# HONDA_BCAN.net
KiCad netlist of a schematic drawn in EAGLE
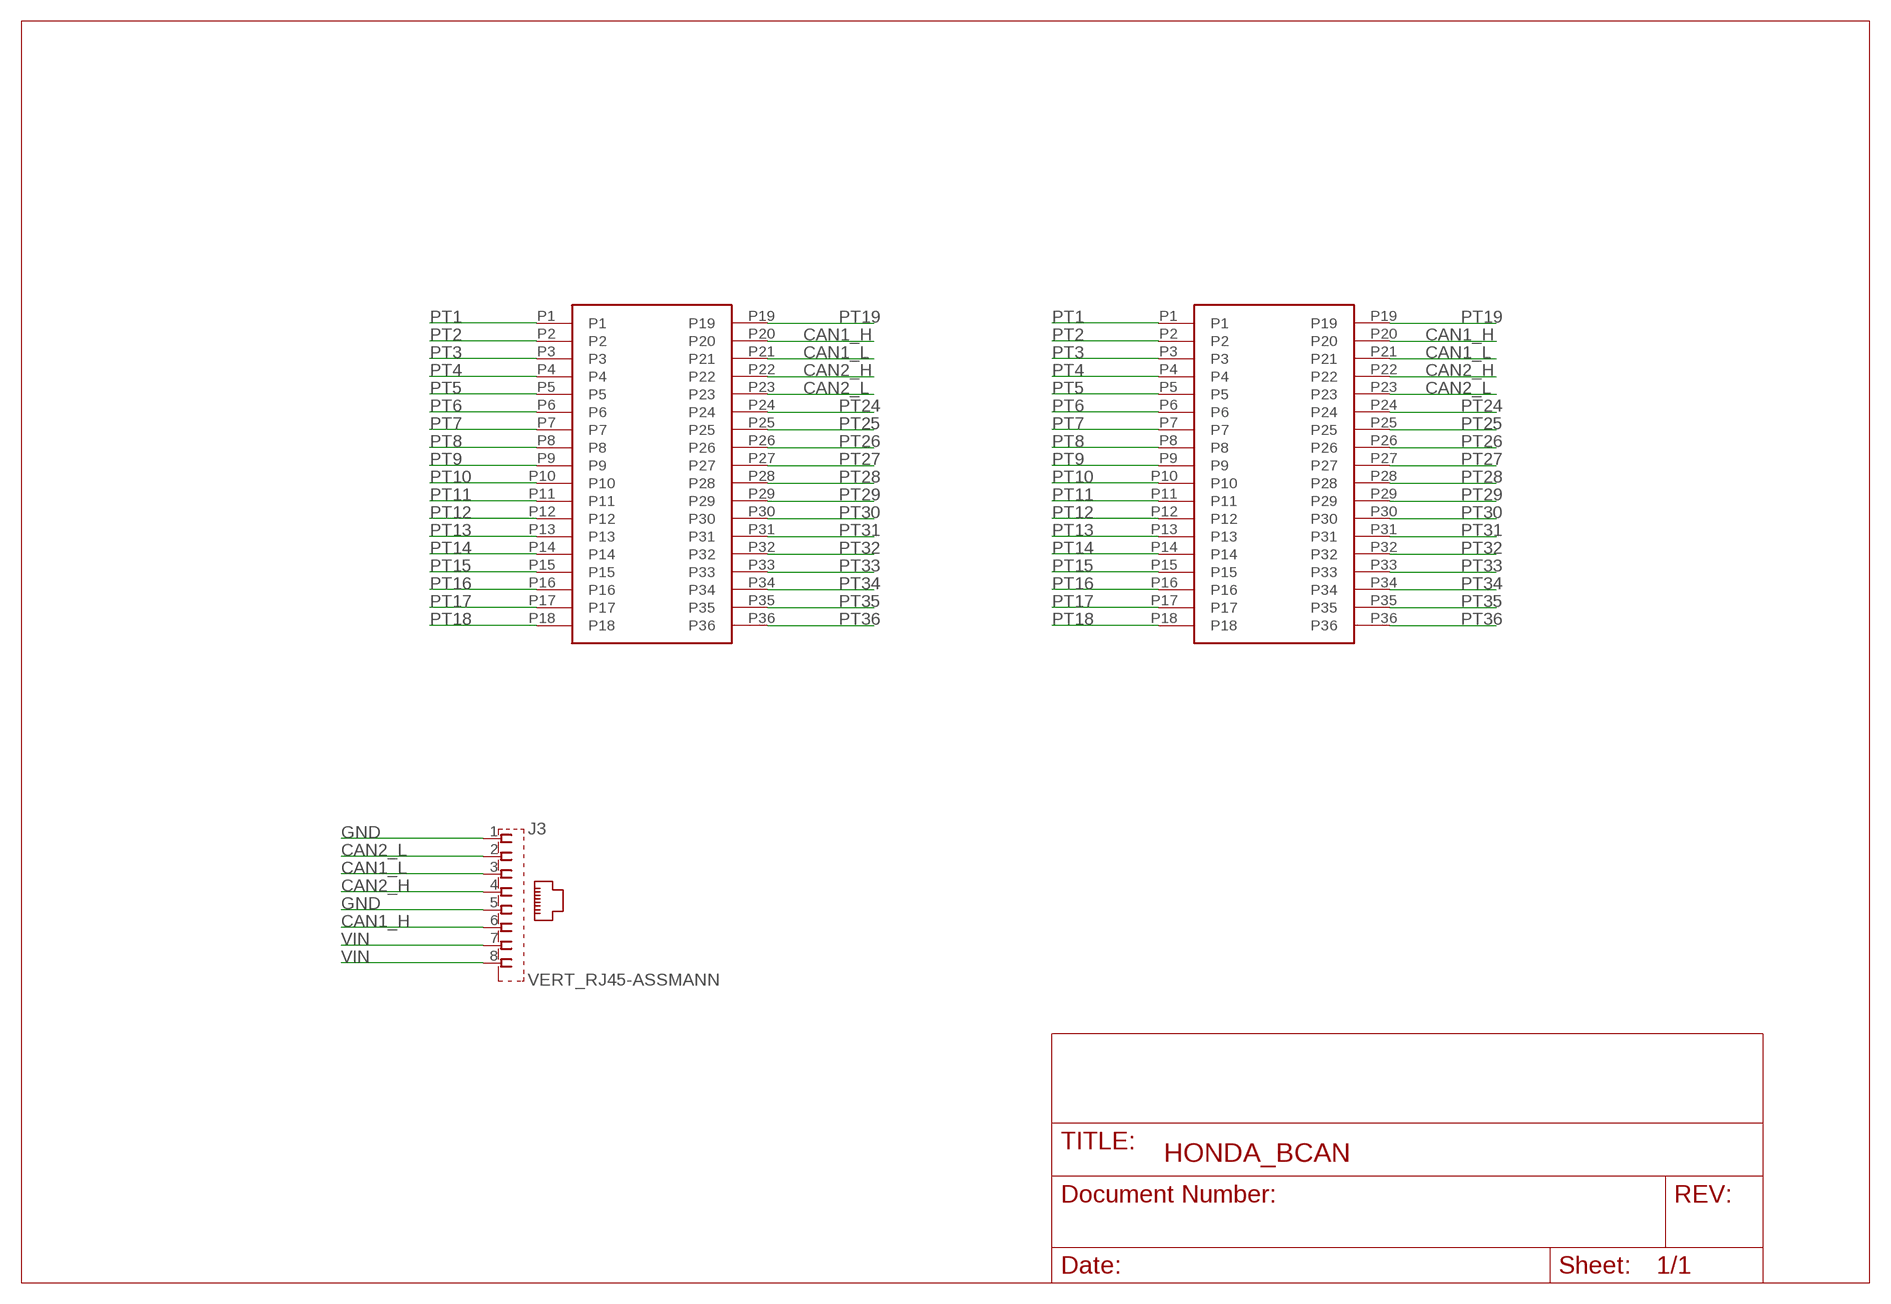
[diagram p0: schematic, sheet 1]

(export (version "E")
  (design (tool "Eeschema 10.0.6"))
  (components
    (comp (ref "J1")
      (value "MX34036NF4")
      (footprint "eagle-import:MX34036NF4")
      (libsource (lib "eagle-import") (part "MX34036NF4"))
    )
    (comp (ref "J2")
      (value "MX34036NF4")
      (footprint "eagle-import:MX34036NF4")
      (libsource (lib "eagle-import") (part "MX34036NF4"))
    )
    (comp (ref "J3")
      (value "VERT_RJ45-ASSMANN")
      (footprint "eagle-import:RJ45-VERT")
      (fields (field (name "MPN") "A-2004-2-4-LPS-N-R"))
      (libsource (lib "eagle-import") (part "VERT_RJ45-ASSMANN"))
    )
  )
  (nets
    (net (code "1") (name "/CAN1_H") (class "Default")
      (node (ref "J1") (pin "P20") (pinfunction "P20_P20") (pintype "bidirectional"))
      (node (ref "J2") (pin "P20") (pinfunction "P20_P20") (pintype "bidirectional"))
      (node (ref "J3") (pin "6") (pinfunction "6_6") (pintype "passive"))
    )
    (net (code "2") (name "/CAN1_L") (class "Default")
      (node (ref "J1") (pin "P21") (pinfunction "P21_P21") (pintype "bidirectional"))
      (node (ref "J2") (pin "P21") (pinfunction "P21_P21") (pintype "bidirectional"))
      (node (ref "J3") (pin "3") (pinfunction "3_3") (pintype "passive"))
    )
    (net (code "3") (name "/CAN2_H") (class "Default")
      (node (ref "J1") (pin "P22") (pinfunction "P22_P22") (pintype "bidirectional"))
      (node (ref "J2") (pin "P22") (pinfunction "P22_P22") (pintype "bidirectional"))
      (node (ref "J3") (pin "4") (pinfunction "4_4") (pintype "passive"))
    )
    (net (code "4") (name "/CAN2_L") (class "Default")
      (node (ref "J1") (pin "P23") (pinfunction "P23_P23") (pintype "bidirectional"))
      (node (ref "J2") (pin "P23") (pinfunction "P23_P23") (pintype "bidirectional"))
      (node (ref "J3") (pin "2") (pinfunction "2_2") (pintype "passive"))
    )
    (net (code "5") (name "/GND") (class "Default")
      (node (ref "J3") (pin "1") (pinfunction "1_1") (pintype "passive"))
      (node (ref "J3") (pin "5") (pinfunction "5_5") (pintype "passive"))
    )
    (net (code "6") (name "/PT1") (class "Default")
      (node (ref "J1") (pin "P1") (pinfunction "P1_P1") (pintype "bidirectional"))
      (node (ref "J2") (pin "P1") (pinfunction "P1_P1") (pintype "bidirectional"))
    )
    (net (code "7") (name "/PT2") (class "Default")
      (node (ref "J1") (pin "P2") (pinfunction "P2_P2") (pintype "bidirectional"))
      (node (ref "J2") (pin "P2") (pinfunction "P2_P2") (pintype "bidirectional"))
    )
    (net (code "8") (name "/PT3") (class "Default")
      (node (ref "J1") (pin "P3") (pinfunction "P3_P3") (pintype "bidirectional"))
      (node (ref "J2") (pin "P3") (pinfunction "P3_P3") (pintype "bidirectional"))
    )
    (net (code "9") (name "/PT4") (class "Default")
      (node (ref "J1") (pin "P4") (pinfunction "P4_P4") (pintype "bidirectional"))
      (node (ref "J2") (pin "P4") (pinfunction "P4_P4") (pintype "bidirectional"))
    )
    (net (code "10") (name "/PT5") (class "Default")
      (node (ref "J1") (pin "P5") (pinfunction "P5_P5") (pintype "bidirectional"))
      (node (ref "J2") (pin "P5") (pinfunction "P5_P5") (pintype "bidirectional"))
    )
    (net (code "11") (name "/PT6") (class "Default")
      (node (ref "J1") (pin "P6") (pinfunction "P6_P6") (pintype "bidirectional"))
      (node (ref "J2") (pin "P6") (pinfunction "P6_P6") (pintype "bidirectional"))
    )
    (net (code "12") (name "/PT7") (class "Default")
      (node (ref "J1") (pin "P7") (pinfunction "P7_P7") (pintype "bidirectional"))
      (node (ref "J2") (pin "P7") (pinfunction "P7_P7") (pintype "bidirectional"))
    )
    (net (code "13") (name "/PT8") (class "Default")
      (node (ref "J1") (pin "P8") (pinfunction "P8_P8") (pintype "bidirectional"))
      (node (ref "J2") (pin "P8") (pinfunction "P8_P8") (pintype "bidirectional"))
    )
    (net (code "14") (name "/PT9") (class "Default")
      (node (ref "J1") (pin "P9") (pinfunction "P9_P9") (pintype "bidirectional"))
      (node (ref "J2") (pin "P9") (pinfunction "P9_P9") (pintype "bidirectional"))
    )
    (net (code "15") (name "/PT10") (class "Default")
      (node (ref "J1") (pin "P10") (pinfunction "P10_P10") (pintype "bidirectional"))
      (node (ref "J2") (pin "P10") (pinfunction "P10_P10") (pintype "bidirectional"))
    )
    (net (code "16") (name "/PT11") (class "Default")
      (node (ref "J1") (pin "P11") (pinfunction "P11_P11") (pintype "bidirectional"))
      (node (ref "J2") (pin "P11") (pinfunction "P11_P11") (pintype "bidirectional"))
    )
    (net (code "17") (name "/PT12") (class "Default")
      (node (ref "J1") (pin "P12") (pinfunction "P12_P12") (pintype "bidirectional"))
      (node (ref "J2") (pin "P12") (pinfunction "P12_P12") (pintype "bidirectional"))
    )
    (net (code "18") (name "/PT13") (class "Default")
      (node (ref "J1") (pin "P13") (pinfunction "P13_P13") (pintype "bidirectional"))
      (node (ref "J2") (pin "P13") (pinfunction "P13_P13") (pintype "bidirectional"))
    )
    (net (code "19") (name "/PT14") (class "Default")
      (node (ref "J1") (pin "P14") (pinfunction "P14_P14") (pintype "bidirectional"))
      (node (ref "J2") (pin "P14") (pinfunction "P14_P14") (pintype "bidirectional"))
    )
    (net (code "20") (name "/PT15") (class "Default")
      (node (ref "J1") (pin "P15") (pinfunction "P15_P15") (pintype "bidirectional"))
      (node (ref "J2") (pin "P15") (pinfunction "P15_P15") (pintype "bidirectional"))
    )
    (net (code "21") (name "/PT16") (class "Default")
      (node (ref "J1") (pin "P16") (pinfunction "P16_P16") (pintype "bidirectional"))
      (node (ref "J2") (pin "P16") (pinfunction "P16_P16") (pintype "bidirectional"))
    )
    (net (code "22") (name "/PT17") (class "Default")
      (node (ref "J1") (pin "P17") (pinfunction "P17_P17") (pintype "bidirectional"))
      (node (ref "J2") (pin "P17") (pinfunction "P17_P17") (pintype "bidirectional"))
    )
    (net (code "23") (name "/PT18") (class "Default")
      (node (ref "J1") (pin "P18") (pinfunction "P18_P18") (pintype "bidirectional"))
      (node (ref "J2") (pin "P18") (pinfunction "P18_P18") (pintype "bidirectional"))
    )
    (net (code "24") (name "/PT19") (class "Default")
      (node (ref "J1") (pin "P19") (pinfunction "P19_P19") (pintype "bidirectional"))
      (node (ref "J2") (pin "P19") (pinfunction "P19_P19") (pintype "bidirectional"))
    )
    (net (code "25") (name "/PT24") (class "Default")
      (node (ref "J1") (pin "P24") (pinfunction "P24_P24") (pintype "bidirectional"))
      (node (ref "J2") (pin "P24") (pinfunction "P24_P24") (pintype "bidirectional"))
    )
    (net (code "26") (name "/PT25") (class "Default")
      (node (ref "J1") (pin "P25") (pinfunction "P25_P25") (pintype "bidirectional"))
      (node (ref "J2") (pin "P25") (pinfunction "P25_P25") (pintype "bidirectional"))
    )
    (net (code "27") (name "/PT26") (class "Default")
      (node (ref "J1") (pin "P26") (pinfunction "P26_P26") (pintype "bidirectional"))
      (node (ref "J2") (pin "P26") (pinfunction "P26_P26") (pintype "bidirectional"))
    )
    (net (code "28") (name "/PT27") (class "Default")
      (node (ref "J1") (pin "P27") (pinfunction "P27_P27") (pintype "bidirectional"))
      (node (ref "J2") (pin "P27") (pinfunction "P27_P27") (pintype "bidirectional"))
    )
    (net (code "29") (name "/PT28") (class "Default")
      (node (ref "J1") (pin "P28") (pinfunction "P28_P28") (pintype "bidirectional"))
      (node (ref "J2") (pin "P28") (pinfunction "P28_P28") (pintype "bidirectional"))
    )
    (net (code "30") (name "/PT29") (class "Default")
      (node (ref "J1") (pin "P29") (pinfunction "P29_P29") (pintype "bidirectional"))
      (node (ref "J2") (pin "P29") (pinfunction "P29_P29") (pintype "bidirectional"))
    )
    (net (code "31") (name "/PT30") (class "Default")
      (node (ref "J1") (pin "P30") (pinfunction "P30_P30") (pintype "bidirectional"))
      (node (ref "J2") (pin "P30") (pinfunction "P30_P30") (pintype "bidirectional"))
    )
    (net (code "32") (name "/PT31") (class "Default")
      (node (ref "J1") (pin "P31") (pinfunction "P31_P31") (pintype "bidirectional"))
      (node (ref "J2") (pin "P31") (pinfunction "P31_P31") (pintype "bidirectional"))
    )
    (net (code "33") (name "/PT32") (class "Default")
      (node (ref "J1") (pin "P32") (pinfunction "P32_P32") (pintype "bidirectional"))
      (node (ref "J2") (pin "P32") (pinfunction "P32_P32") (pintype "bidirectional"))
    )
    (net (code "34") (name "/PT33") (class "Default")
      (node (ref "J1") (pin "P33") (pinfunction "P33_P33") (pintype "bidirectional"))
      (node (ref "J2") (pin "P33") (pinfunction "P33_P33") (pintype "bidirectional"))
    )
    (net (code "35") (name "/PT34") (class "Default")
      (node (ref "J1") (pin "P34") (pinfunction "P34_P34") (pintype "bidirectional"))
      (node (ref "J2") (pin "P34") (pinfunction "P34_P34") (pintype "bidirectional"))
    )
    (net (code "36") (name "/PT35") (class "Default")
      (node (ref "J1") (pin "P35") (pinfunction "P35_P35") (pintype "bidirectional"))
      (node (ref "J2") (pin "P35") (pinfunction "P35_P35") (pintype "bidirectional"))
    )
    (net (code "37") (name "/PT36") (class "Default")
      (node (ref "J1") (pin "P36") (pinfunction "P36_P36") (pintype "bidirectional"))
      (node (ref "J2") (pin "P36") (pinfunction "P36_P36") (pintype "bidirectional"))
    )
    (net (code "38") (name "/VIN") (class "Default")
      (node (ref "J3") (pin "7") (pinfunction "7_7") (pintype "passive"))
      (node (ref "J3") (pin "8") (pinfunction "8_8") (pintype "passive"))
    )
  )
)
